# Main_board.net
KiCad netlist of a schematic drawn in EAGLE
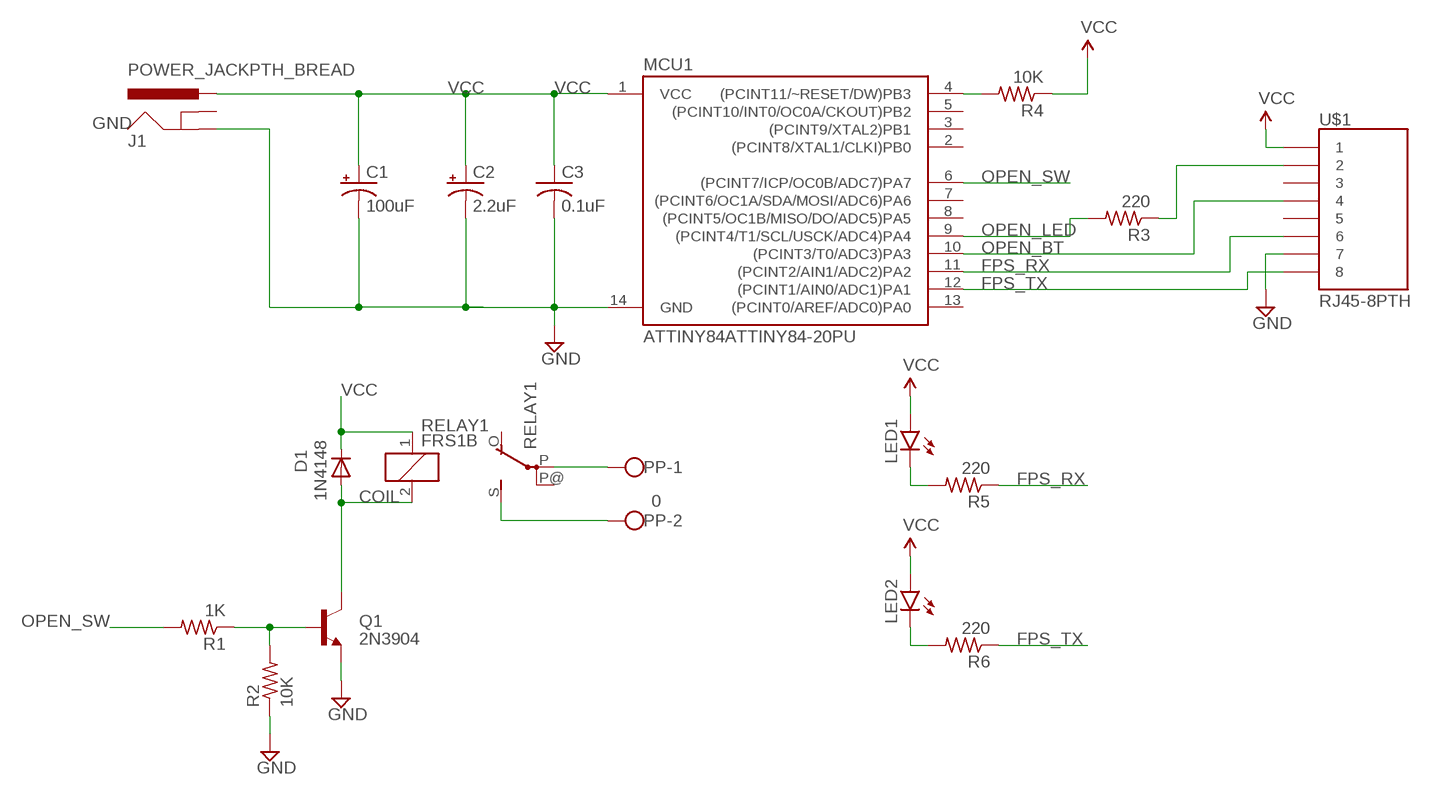
[diagram p0: schematic, sheet 1]

(export (version "E")
  (design (tool "Eeschema 10.0.6"))
  (components
    (comp (ref "C1")
      (value "100uF")
      (footprint "eagle-import:CPOL-RADIAL-10UF-25V")
      (libsource (lib "eagle-import") (part "CAP_POLPTH2"))
    )
    (comp (ref "C2")
      (value "2.2uF")
      (footprint "eagle-import:CPOL-RADIAL-10UF-25V")
      (libsource (lib "eagle-import") (part "CAP_POLPTH2"))
    )
    (comp (ref "C3")
      (value "0.1uF")
      (footprint "eagle-import:C025-024X044")
      (libsource (lib "eagle-import") (part "C-US025-024X044"))
    )
    (comp (ref "D1")
      (value "1N4148")
      (footprint "eagle-import:DIODE-1N4148")
      (libsource (lib "eagle-import") (part "DIODE1N4148"))
    )
    (comp (ref "J1")
      (value "POWER_JACKPTH_BREAD")
      (footprint "eagle-import:POWER_JACK_PTH_BREAD")
      (libsource (lib "eagle-import") (part "POWER_JACKPTH_BREAD"))
    )
    (comp (ref "LED1")
      (value "LED3MM")
      (footprint "eagle-import:LED3MM")
      (libsource (lib "eagle-import") (part "LED3MM"))
    )
    (comp (ref "LED2")
      (value "LED3MM")
      (footprint "eagle-import:LED3MM")
      (libsource (lib "eagle-import") (part "LED3MM"))
    )
    (comp (ref "MCU1")
      (value "ATTINY84ATTINY84-20PU")
      (footprint "eagle-import:DIL14")
      (libsource (lib "eagle-import") (part "ATTINY84ATTINY84-20PU"))
    )
    (comp (ref "PP")
      (value "0")
      (footprint "eagle-import:W237-102")
      (libsource (lib "eagle-import") (part "W237-102"))
    )
    (comp (ref "Q1")
      (value "2N3904")
      (footprint "eagle-import:TO-92")
      (libsource (lib "eagle-import") (part "TRANSISTOR_NPNTO92"))
    )
    (comp (ref "R1")
      (value "1K")
      (footprint "eagle-import:0207_10")
      (libsource (lib "eagle-import") (part "R-US_0207/10"))
    )
    (comp (ref "R2")
      (value "10K")
      (footprint "eagle-import:0207_10")
      (libsource (lib "eagle-import") (part "R-US_0207/10"))
    )
    (comp (ref "R3")
      (value "220")
      (footprint "eagle-import:0207_10")
      (libsource (lib "eagle-import") (part "R-US_0207/10"))
    )
    (comp (ref "R4")
      (value "10K")
      (footprint "eagle-import:0207_10")
      (libsource (lib "eagle-import") (part "R-US_0207/10"))
    )
    (comp (ref "R5")
      (value "220")
      (footprint "eagle-import:0207_10")
      (libsource (lib "eagle-import") (part "R-US_0207/10"))
    )
    (comp (ref "R6")
      (value "220")
      (footprint "eagle-import:0207_10")
      (libsource (lib "eagle-import") (part "R-US_0207/10"))
    )
    (comp (ref "RELAY1")
      (value "FRS1B")
      (footprint "eagle-import:FRS1B")
      (libsource (lib "eagle-import") (part "FRS1B"))
    )
    (comp (ref "U$1")
      (value "RJ45-8PTH")
      (footprint "eagle-import:RJ45-8")
      (libsource (lib "eagle-import") (part "RJ45-8PTH"))
    )
  )
  (nets
    (net (code "1") (name "/COIL") (class "Default")
      (node (ref "D1") (pin "A") (pinfunction "A_A") (pintype "passive"))
      (node (ref "Q1") (pin "3") (pinfunction "C_3") (pintype "passive"))
      (node (ref "RELAY1") (pin "2") (pinfunction "2_2") (pintype "passive"))
    )
    (net (code "2") (name "/FPS_RX") (class "Default")
      (node (ref "MCU1") (pin "11") (pinfunction "(PCINT2/AIN1/ADC2)PA2_11") (pintype "bidirectional"))
      (node (ref "R5") (pin "1") (pinfunction "1_1") (pintype "passive"))
      (node (ref "U$1") (pin "6") (pinfunction "6_6") (pintype "bidirectional"))
    )
    (net (code "3") (name "/FPS_TX") (class "Default")
      (node (ref "MCU1") (pin "12") (pinfunction "(PCINT1/AIN0/ADC1)PA1_12") (pintype "bidirectional"))
      (node (ref "R6") (pin "1") (pinfunction "1_1") (pintype "passive"))
      (node (ref "U$1") (pin "8") (pinfunction "8_8") (pintype "bidirectional"))
    )
    (net (code "4") (name "/OPEN_BT") (class "Default")
      (node (ref "MCU1") (pin "10") (pinfunction "(PCINT3/T0/ADC3)PA3_10") (pintype "bidirectional"))
      (node (ref "U$1") (pin "4") (pinfunction "4_4") (pintype "bidirectional"))
    )
    (net (code "5") (name "/OPEN_LED") (class "Default")
      (node (ref "MCU1") (pin "9") (pinfunction "(PCINT4/T1/SCL/USCK/ADC4)PA4_9") (pintype "bidirectional"))
      (node (ref "R3") (pin "2") (pinfunction "2_2") (pintype "passive"))
    )
    (net (code "6") (name "/OPEN_SW") (class "Default")
      (node (ref "MCU1") (pin "6") (pinfunction "(PCINT7/ICP/OC0B/ADC7)PA7_6") (pintype "bidirectional"))
      (node (ref "R1") (pin "2") (pinfunction "2_2") (pintype "passive"))
    )
    (net (code "7") (name "GND") (class "Default")
      (node (ref "C1") (pin "2") (pinfunction "-_2") (pintype "passive"))
      (node (ref "C2") (pin "2") (pinfunction "-_2") (pintype "passive"))
      (node (ref "C3") (pin "2") (pinfunction "2_2") (pintype "passive"))
      (node (ref "J1") (pin "GND") (pinfunction "GND_GND") (pintype "bidirectional"))
      (node (ref "MCU1") (pin "14") (pinfunction "GND_14") (pintype "bidirectional"))
      (node (ref "Q1") (pin "1") (pinfunction "E_1") (pintype "passive"))
      (node (ref "R2") (pin "1") (pinfunction "1_1") (pintype "passive"))
      (node (ref "U$1") (pin "7") (pinfunction "7_7") (pintype "bidirectional"))
    )
    (net (code "8") (name "Net-(LED1-C)") (class "Default")
      (node (ref "LED1") (pin "K") (pinfunction "C_K") (pintype "passive"))
      (node (ref "R5") (pin "2") (pinfunction "2_2") (pintype "passive"))
    )
    (net (code "9") (name "Net-(LED2-C)") (class "Default")
      (node (ref "LED2") (pin "K") (pinfunction "C_K") (pintype "passive"))
      (node (ref "R6") (pin "2") (pinfunction "2_2") (pintype "passive"))
    )
    (net (code "10") (name "Net-(MCU1-(PCINT11{slash}~{RESET{slash}DW})PB3)") (class "Default")
      (node (ref "MCU1") (pin "4") (pinfunction "(PCINT11/~{RESET/DW})PB3_4") (pintype "bidirectional"))
      (node (ref "R4") (pin "2") (pinfunction "2_2") (pintype "passive"))
    )
    (net (code "11") (name "Net-(PPA-KL)") (class "Default")
      (node (ref "PP") (pin "1") (pinfunction "KL_1") (pintype "passive"))
      (node (ref "RELAY1") (pin "P") (pinfunction "P_P") (pintype "passive"))
    )
    (net (code "12") (name "Net-(PPB-KL)") (class "Default")
      (node (ref "PP") (pin "2") (pinfunction "KL_2") (pintype "passive"))
      (node (ref "RELAY1") (pin "S") (pinfunction "S_S") (pintype "passive"))
    )
    (net (code "13") (name "Net-(Q1-B)") (class "Default")
      (node (ref "Q1") (pin "2") (pinfunction "B_2") (pintype "passive"))
      (node (ref "R1") (pin "1") (pinfunction "1_1") (pintype "passive"))
      (node (ref "R2") (pin "2") (pinfunction "2_2") (pintype "passive"))
    )
    (net (code "14") (name "Net-(R3-Pad1)") (class "Default")
      (node (ref "R3") (pin "1") (pinfunction "1_1") (pintype "passive"))
      (node (ref "U$1") (pin "2") (pinfunction "2_2") (pintype "bidirectional"))
    )
    (net (code "15") (name "VCC") (class "Default")
      (node (ref "C1") (pin "1") (pinfunction "+_1") (pintype "passive"))
      (node (ref "C2") (pin "1") (pinfunction "+_1") (pintype "passive"))
      (node (ref "C3") (pin "1") (pinfunction "1_1") (pintype "passive"))
      (node (ref "D1") (pin "C") (pinfunction "C_C") (pintype "passive"))
      (node (ref "J1") (pin "PWR") (pinfunction "PWR_PWR") (pintype "bidirectional"))
      (node (ref "LED1") (pin "A") (pinfunction "A_A") (pintype "passive"))
      (node (ref "LED2") (pin "A") (pinfunction "A_A") (pintype "passive"))
      (node (ref "MCU1") (pin "1") (pinfunction "VCC_1") (pintype "bidirectional"))
      (node (ref "R4") (pin "1") (pinfunction "1_1") (pintype "passive"))
      (node (ref "RELAY1") (pin "1") (pinfunction "1_1") (pintype "passive"))
      (node (ref "U$1") (pin "1") (pinfunction "1_1") (pintype "bidirectional"))
    )
    (net (code "16") (name "unconnected-(J1-PadGNDBREAK)") (class "Default")
      (node (ref "J1") (pin "GNDBREAK") (pinfunction "GNDBREAK_GNDBREAK") (pintype "bidirectional"))
    )
    (net (code "17") (name "unconnected-(MCU1-(PCINT0{slash}AREF{slash}ADC0)PA0-Pad13)") (class "Default")
      (node (ref "MCU1") (pin "13") (pinfunction "(PCINT0/AREF/ADC0)PA0_13") (pintype "bidirectional"))
    )
    (net (code "18") (name "unconnected-(MCU1-(PCINT5{slash}OC1B{slash}MISO{slash}DO{slash}ADC5)PA5-Pad8)") (class "Default")
      (node (ref "MCU1") (pin "8") (pinfunction "(PCINT5/OC1B/MISO/DO/ADC5)PA5_8") (pintype "bidirectional"))
    )
    (net (code "19") (name "unconnected-(MCU1-(PCINT6{slash}OC1A{slash}SDA{slash}MOSI{slash}ADC6)PA6-Pad7)") (class "Default")
      (node (ref "MCU1") (pin "7") (pinfunction "(PCINT6/OC1A/SDA/MOSI/ADC6)PA6_7") (pintype "bidirectional"))
    )
    (net (code "20") (name "unconnected-(MCU1-(PCINT8{slash}XTAL1{slash}CLKI)PB0-Pad2)") (class "Default")
      (node (ref "MCU1") (pin "2") (pinfunction "(PCINT8/XTAL1/CLKI)PB0_2") (pintype "bidirectional"))
    )
    (net (code "21") (name "unconnected-(MCU1-(PCINT9{slash}XTAL2)PB1-Pad3)") (class "Default")
      (node (ref "MCU1") (pin "3") (pinfunction "(PCINT9/XTAL2)PB1_3") (pintype "bidirectional"))
    )
    (net (code "22") (name "unconnected-(MCU1-(PCINT10{slash}INT0{slash}OC0A{slash}CKOUT)PB2-Pad5)") (class "Default")
      (node (ref "MCU1") (pin "5") (pinfunction "(PCINT10/INT0/OC0A/CKOUT)PB2_5") (pintype "bidirectional"))
    )
    (net (code "23") (name "unconnected-(RELAY1-PadO)") (class "Default")
      (node (ref "RELAY1") (pin "O") (pinfunction "O_O") (pintype "passive"))
    )
    (net (code "24") (name "unconnected-(RELAY1B-P-PadP@)") (class "Default")
      (node (ref "RELAY1") (pin "P@") (pinfunction "P_P@") (pintype "passive"))
    )
    (net (code "25") (name "unconnected-(U$1-Pad3)") (class "Default")
      (node (ref "U$1") (pin "3") (pinfunction "3_3") (pintype "bidirectional"))
    )
    (net (code "26") (name "unconnected-(U$1-Pad5)") (class "Default")
      (node (ref "U$1") (pin "5") (pinfunction "5_5") (pintype "bidirectional"))
    )
  )
)
